# configuration_SCAM.net
KiCad netlist of a schematic drawn in Altium Designer
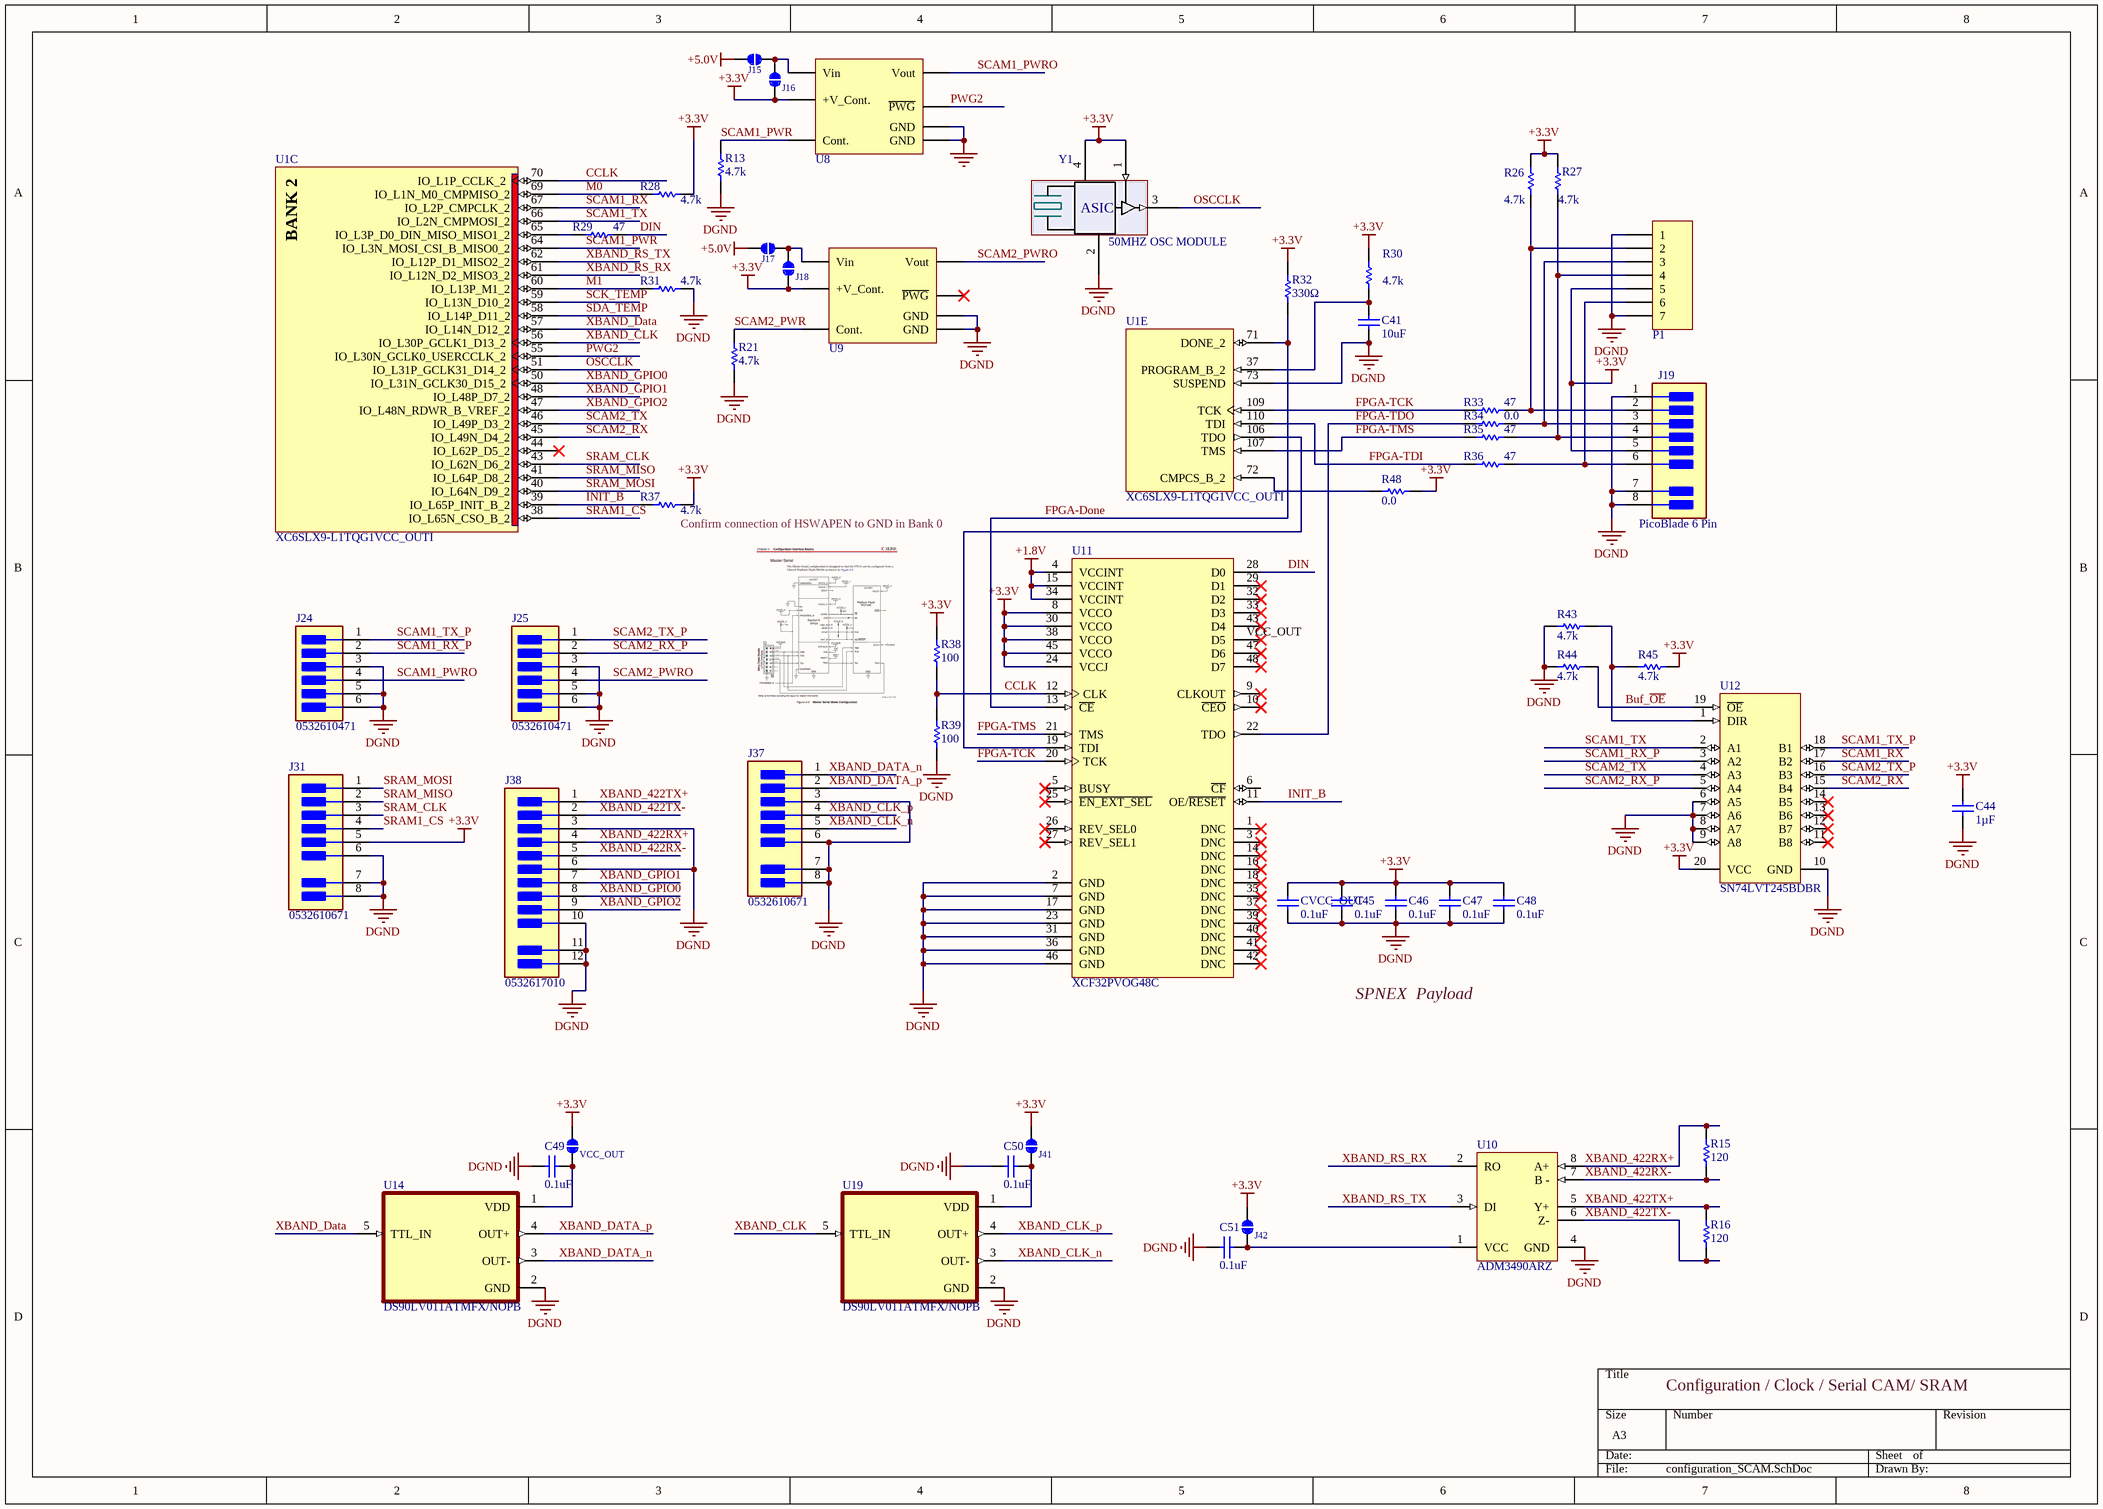
[diagram p0: configuration_SCAM.SchDoc]

(export (version "E")
  (design (tool "Eeschema 10.0.6"))
  (components
    (comp (ref "C41")
      (value "10uF")
      (footprint "capc3216n")
      (description "Capacitor")
      (fields (field (name "Comment") "Cap Semi"))
      (libsource (lib "Spnex_lib") (part "Cap_CER_10U_10V_1206"))
    )
    (comp (ref "C44")
      (value "Cap_CER_1U_10V_0603")
      (footprint "0603CAP")
      (description "Capacitor")
      (fields
        (field (name "MANUFACTURER") "Taiyo Yuden")
        (field (name "MANUFACTURER PART NUMBER") "LMK107B7105KA-T")
        (field (name "CAPACITANCE") "1µF")
      )
      (libsource (lib "SPNeX_NewPL") (part "Cap_CER_1U_10V_0603"))
    )
    (comp (ref "C45")
      (value "0.1uF")
      (footprint "0805CAP")
      (description "Surface Mount Ceramic Multilayer Capacitor 0.1uF 10% X7R 16V 0805 Paper T/R")
      (fields
        (field (name "MANUFACTURER") "Yageo")
        (field (name "MANUFACTURER PART NUMBER") "CC0805KRX7R7BB104")
      )
      (libsource (lib "SPNeX_NewPL") (part "CAP_CER_0.1uf_10V_0805"))
    )
    (comp (ref "C46")
      (value "0.1uF")
      (footprint "0805CAP")
      (description "Surface Mount Ceramic Multilayer Capacitor 0.1uF 10% X7R 16V 0805 Paper T/R")
      (fields
        (field (name "MANUFACTURER") "Yageo")
        (field (name "MANUFACTURER PART NUMBER") "CC0805KRX7R7BB104")
      )
      (libsource (lib "SPNeX_NewPL") (part "CAP_CER_0.1uf_10V_0805"))
    )
    (comp (ref "C47")
      (value "0.1uF")
      (footprint "0805CAP")
      (description "Surface Mount Ceramic Multilayer Capacitor 0.1uF 10% X7R 16V 0805 Paper T/R")
      (fields
        (field (name "MANUFACTURER") "Yageo")
        (field (name "MANUFACTURER PART NUMBER") "CC0805KRX7R7BB104")
      )
      (libsource (lib "SPNeX_NewPL") (part "CAP_CER_0.1uf_10V_0805"))
    )
    (comp (ref "C48")
      (value "0.1uF")
      (footprint "0805CAP")
      (description "Surface Mount Ceramic Multilayer Capacitor 0.1uF 10% X7R 16V 0805 Paper T/R")
      (fields
        (field (name "MANUFACTURER") "Yageo")
        (field (name "MANUFACTURER PART NUMBER") "CC0805KRX7R7BB104")
      )
      (libsource (lib "SPNeX_NewPL") (part "CAP_CER_0.1uf_10V_0805"))
    )
    (comp (ref "C49")
      (value "0.1uF")
      (footprint "0805CAP")
      (description "Surface Mount Ceramic Multilayer Capacitor 0.1uF 10% X7R 16V 0805 Paper T/R")
      (fields
        (field (name "MANUFACTURER") "Yageo")
        (field (name "MANUFACTURER PART NUMBER") "CC0805KRX7R7BB104")
      )
      (libsource (lib "SPNeX_NewPL") (part "CAP_CER_0.1uf_10V_0805"))
    )
    (comp (ref "C50")
      (value "0.1uF")
      (footprint "0805 - CAP")
      (description "CAP CER 0.1UF 16V X7R 0805")
      (fields
        (field (name "MANUFACTURER") "Samsung Electro-Mechanics America, Inc.")
        (field (name "MANUFACTURER PART NUMBER") "CL21B104KOANNNC")
      )
      (libsource (lib "Kh_Lib") (part "Cap_CER_0.1U_16V_0805"))
    )
    (comp (ref "C51")
      (value "0.1uF")
      (footprint "0805 - CAP")
      (description "CAP CER 0.1UF 16V X7R 0805")
      (fields
        (field (name "MANUFACTURER") "Samsung Electro-Mechanics America, Inc.")
        (field (name "MANUFACTURER PART NUMBER") "CL21B104KOANNNC")
      )
      (libsource (lib "Kh_Lib") (part "Cap_CER_0.1U_16V_0805"))
    )
    (comp (ref "CVCC_OUT")
      (value "0.1uF")
      (footprint "0805CAP")
      (description "Surface Mount Ceramic Multilayer Capacitor 0.1uF 10% X7R 16V 0805 Paper T/R")
      (fields
        (field (name "MANUFACTURER") "Yageo")
        (field (name "MANUFACTURER PART NUMBER") "CC0805KRX7R7BB104")
      )
      (libsource (lib "SPNeX_NewPL") (part "CAP_CER_0.1uf_10V_0805"))
    )
    (comp (ref "J15")
      (value "JUMPER")
      (footprint "SJMP")
      (description "OPTION SELECTION PAD")
      (libsource (lib "") (part "JUMPER_1"))
    )
    (comp (ref "J16")
      (value "JUMPER")
      (footprint "SJMP")
      (description "OPTION SELECTION PAD")
      (libsource (lib "Spnex_lib") (part "JUMPER"))
    )
    (comp (ref "J17")
      (value "JUMPER")
      (footprint "SJMP")
      (description "OPTION SELECTION PAD")
      (libsource (lib "") (part "JUMPER_1"))
    )
    (comp (ref "J18")
      (value "JUMPER")
      (footprint "SJMP")
      (description "OPTION SELECTION PAD")
      (libsource (lib "Spnex_lib") (part "JUMPER"))
    )
    (comp (ref "J19")
      (value "PicoBlade 6 Pin")
      (footprint "Molex_6RA_MFG")
      (description "1.25mm (.049\") Pitch PicoBlade Header, Surface Mount, Right Angle, Lead-free, 6 Circuits")
      (fields (field (name "MANUFACTURER") "Molex") (field (name "MANUFACTURER PART NUMBER") "0532610671"))
      (libsource (lib "Spnex_lib") (part "0532610671"))
    )
    (comp (ref "J24")
      (value "0532610471")
      (footprint "Molex_4RA_MFG")
      (description "Conn Shrouded Header (4 Sides) HDR 4 POS 1.25mm Solder RA Side Entry SMD PicoBlade™ T/R")
      (fields (field (name "MANUFACTURER") "Molex") (field (name "MANUFACTURER PART NUMBER") "53261-0471"))
      (libsource (lib "SPNeX_NewPL") (part "0532610471"))
    )
    (comp (ref "J25")
      (value "0532610471")
      (footprint "Molex_4RA_MFG")
      (description "Conn Shrouded Header (4 Sides) HDR 4 POS 1.25mm Solder RA Side Entry SMD PicoBlade™ T/R")
      (fields (field (name "MANUFACTURER") "Molex") (field (name "MANUFACTURER PART NUMBER") "53261-0471"))
      (libsource (lib "SPNeX_NewPL") (part "0532610471"))
    )
    (comp (ref "J31")
      (value "0532610671")
      (footprint "Molex_6RA_MFG")
      (description "1.25mm (.049\") Pitch PicoBlade Header, Surface Mount, Right Angle, Lead-free, 6 Circuits")
      (fields (field (name "MANUFACTURER") "Molex"))
      (libsource (lib "Spnex_library") (part "0532610671"))
    )
    (comp (ref "J37")
      (value "0532610671")
      (footprint "Molex_6RA_MFG")
      (description "1.25mm (.049\") Pitch PicoBlade Header, Surface Mount, Right Angle, Lead-free, 6 Circuits")
      (fields (field (name "MANUFACTURER") "Molex"))
      (libsource (lib "Spnex_library") (part "0532610671"))
    )
    (comp (ref "J38")
      (value "0532617010")
      (footprint "Molex_10RA")
      (fields (field (name "MANUFACTURER") "Molex"))
      (libsource (lib "Spnex_library") (part "0532617010"))
    )
    (comp (ref "J41")
      (value "JUMPER")
      (footprint "SJMP")
      (description "OPTION SELECTION PAD")
      (libsource (lib "Kh_Lib") (part "JUMPER"))
    )
    (comp (ref "J42")
      (value "JUMPER")
      (footprint "SJMP")
      (description "OPTION SELECTION PAD")
      (libsource (lib "Kh_Lib") (part "JUMPER"))
    )
    (comp (ref "P1")
      (value "Header 7")
      (footprint "HDR1X7F")
      (description "Header, 7-Pin")
      (fields (field (name "PUBLISHER") "Altium Limited"))
      (libsource (lib "Spnex_lib") (part "Header 7"))
    )
    (comp (ref "R13")
      (value "RES_4.7K_0.1W_0603")
      (footprint "0603RES")
      (description "Resistor")
      (fields
        (field (name "MANUFACTURER") "Stackpole Electronics Inc.")
        (field (name "MANUFACTURER PART NUMBER") "RMCF0603JT4K70")
        (field (name "RESISTANCE (OHMS)") "4.7k")
      )
      (libsource (lib "Spnex_lib") (part "RES_4.7K_0.1W_0603"))
    )
    (comp (ref "R15")
      (value "RES_120_0.25W_0603")
      (footprint "0603RES")
      (description "RES SMD 120 OHM 5% 1/4W 0603")
      (fields
        (field (name "MANUFACTURER") "Rohm Semiconductor")
        (field (name "MANUFACTURER PART NUMBER") "ESR03EZPJ121")
        (field (name "RESISTANCE (OHMS)") "120")
      )
      (libsource (lib "Spnex_library") (part "RES_120_0.25W_0603"))
    )
    (comp (ref "R16")
      (value "RES_120_0.25W_0603")
      (footprint "0603RES")
      (description "RES SMD 120 OHM 5% 1/4W 0603")
      (fields
        (field (name "MANUFACTURER") "Rohm Semiconductor")
        (field (name "MANUFACTURER PART NUMBER") "ESR03EZPJ121")
        (field (name "RESISTANCE (OHMS)") "120")
      )
      (libsource (lib "Spnex_library") (part "RES_120_0.25W_0603"))
    )
    (comp (ref "R21")
      (value "RES_4.7K_0.1W_0603")
      (footprint "0603RES")
      (description "Resistor")
      (fields
        (field (name "MANUFACTURER") "Stackpole Electronics Inc.")
        (field (name "MANUFACTURER PART NUMBER") "RMCF0603JT4K70")
        (field (name "RESISTANCE (OHMS)") "4.7k")
      )
      (libsource (lib "Spnex_lib") (part "RES_4.7K_0.1W_0603"))
    )
    (comp (ref "R26")
      (value "RES_4.7K_0.1W_0603")
      (footprint "0603RES")
      (description "Resistor")
      (fields
        (field (name "MANUFACTURER") "Stackpole Electronics Inc.")
        (field (name "MANUFACTURER PART NUMBER") "RMCF0603JT4K70")
        (field (name "RESISTANCE (OHMS)") "4.7k")
      )
      (libsource (lib "Spnex_lib") (part "RES_4.7K_0.1W_0603"))
    )
    (comp (ref "R27")
      (value "RES_4.7K_0.1W_0603")
      (footprint "0603RES")
      (description "Resistor")
      (fields
        (field (name "MANUFACTURER") "Stackpole Electronics Inc.")
        (field (name "MANUFACTURER PART NUMBER") "RMCF0603JT4K70")
        (field (name "RESISTANCE (OHMS)") "4.7k")
      )
      (libsource (lib "Spnex_lib") (part "RES_4.7K_0.1W_0603"))
    )
    (comp (ref "R28")
      (value "RES_4.7K_0.1W_0603")
      (footprint "0603RES")
      (description "Resistor")
      (fields
        (field (name "MANUFACTURER") "Stackpole Electronics Inc.")
        (field (name "MANUFACTURER PART NUMBER") "RMCF0603JT4K70")
        (field (name "RESISTANCE (OHMS)") "4.7k")
      )
      (libsource (lib "Spnex_lib") (part "RES_4.7K_0.1W_0603"))
    )
    (comp (ref "R29")
      (value "RES_47R_0.25W_0805")
      (footprint "0603RES")
      (description "RES SMD 47 OHM 5% 0.4W 0805")
      (fields
        (field (name "MANUFACTURER") "Rohm Semiconductor")
        (field (name "MANUFACTURER PART NUMBER") "ESR10EZPJ470")
        (field (name "RESISTANCE (OHMS)") "47")
      )
      (libsource (lib "Spnex_lib") (part "RES_47R_0.25W_0805"))
    )
    (comp (ref "R30")
      (value "RES_4.7K_0.1W_0603")
      (footprint "0603RES")
      (description "Resistor")
      (fields
        (field (name "MANUFACTURER") "Stackpole Electronics Inc.")
        (field (name "MANUFACTURER PART NUMBER") "RMCF0603JT4K70")
        (field (name "RESISTANCE (OHMS)") "4.7k")
      )
      (libsource (lib "Spnex_lib") (part "RES_4.7K_0.1W_0603"))
    )
    (comp (ref "R31")
      (value "RES_4.7K_0.1W_0603")
      (footprint "0603RES")
      (description "Resistor")
      (fields
        (field (name "MANUFACTURER") "Stackpole Electronics Inc.")
        (field (name "MANUFACTURER PART NUMBER") "RMCF0603JT4K70")
        (field (name "RESISTANCE (OHMS)") "4.7k")
      )
      (libsource (lib "Spnex_lib") (part "RES_4.7K_0.1W_0603"))
    )
    (comp (ref "R32")
      (value "RES_330 Ohm_0603")
      (footprint "0603")
      (description "Res Thick Film 0603 330 Ohm 5% 0.1W(1/10W) +/-200ppm/ßC Pad SMD Automotive T/R")
      (fields
        (field (name "MANUFACTURER") "Panasonic")
        (field (name "MANUFACTURER PART NUMBER") "ERJ-3GEYJ331V")
        (field (name "RESISTANCE") "330Ω")
      )
      (libsource (lib "Spnex_lib") (part "RES_330 Ohm_0603"))
    )
    (comp (ref "R33")
      (value "RES_47R_0.25W_0805")
      (footprint "0603RES")
      (description "RES SMD 47 OHM 5% 0.4W 0805")
      (fields
        (field (name "MANUFACTURER") "Rohm Semiconductor")
        (field (name "MANUFACTURER PART NUMBER") "ESR10EZPJ470")
        (field (name "RESISTANCE (OHMS)") "47")
      )
      (libsource (lib "Spnex_lib") (part "RES_47R_0.25W_0805"))
    )
    (comp (ref "R34")
      (value "RES_0_0.1W_0603")
      (footprint "0603RES")
      (description "Resistor")
      (fields
        (field (name "MANUFACTURER") "Samsung Electro-Mechanics America, Inc.")
        (field (name "MANUFACTURER PART NUMBER") "RC1608J000CS")
        (field (name "RESISTANCE (OHMS)") "0.0")
      )
      (libsource (lib "Spnex_lib") (part "RES_0_0.1W_0603"))
    )
    (comp (ref "R35")
      (value "RES_47R_0.25W_0805")
      (footprint "0603RES")
      (description "RES SMD 47 OHM 5% 0.4W 0805")
      (fields
        (field (name "MANUFACTURER") "Rohm Semiconductor")
        (field (name "MANUFACTURER PART NUMBER") "ESR10EZPJ470")
        (field (name "RESISTANCE (OHMS)") "47")
      )
      (libsource (lib "Spnex_lib") (part "RES_47R_0.25W_0805"))
    )
    (comp (ref "R36")
      (value "RES_47R_0.25W_0805")
      (footprint "0603RES")
      (description "RES SMD 47 OHM 5% 0.4W 0805")
      (fields
        (field (name "MANUFACTURER") "Rohm Semiconductor")
        (field (name "MANUFACTURER PART NUMBER") "ESR10EZPJ470")
        (field (name "RESISTANCE (OHMS)") "47")
      )
      (libsource (lib "Spnex_lib") (part "RES_47R_0.25W_0805"))
    )
    (comp (ref "R37")
      (value "RES_4.7K_0.1W_0603")
      (footprint "0603RES")
      (description "Resistor")
      (fields
        (field (name "MANUFACTURER") "Stackpole Electronics Inc.")
        (field (name "MANUFACTURER PART NUMBER") "RMCF0603JT4K70")
        (field (name "RESISTANCE (OHMS)") "4.7k")
      )
      (libsource (lib "Spnex_lib") (part "RES_4.7K_0.1W_0603"))
    )
    (comp (ref "R38")
      (value "RES_100_0.1W_0603")
      (footprint "0603RES")
      (description "Resistor")
      (fields
        (field (name "MANUFACTURER") "Stackpole Electronics Inc.")
        (field (name "MANUFACTURER PART NUMBER") "RMCF0603JT100R")
        (field (name "RESISTANCE (OHMS)") "100")
      )
      (libsource (lib "Spnex_lib") (part "RES_100_0.1W_0603"))
    )
    (comp (ref "R39")
      (value "RES_100_0.1W_0603")
      (footprint "0603RES")
      (description "Resistor")
      (fields
        (field (name "MANUFACTURER") "Stackpole Electronics Inc.")
        (field (name "MANUFACTURER PART NUMBER") "RMCF0603JT100R")
        (field (name "RESISTANCE (OHMS)") "100")
      )
      (libsource (lib "Spnex_lib") (part "RES_100_0.1W_0603"))
    )
    (comp (ref "R43")
      (value "RES_4.7K_0.1W_0603")
      (footprint "0603RES")
      (description "Resistor")
      (fields
        (field (name "MANUFACTURER") "Stackpole Electronics Inc.")
        (field (name "MANUFACTURER PART NUMBER") "RMCF0603JT4K70")
        (field (name "RESISTANCE (OHMS)") "4.7k")
      )
      (libsource (lib "SPNeX_NewPL") (part "RES_4.7K_0.1W_0603"))
    )
    (comp (ref "R44")
      (value "RES_4.7K_0.1W_0603")
      (footprint "0603RES")
      (description "Resistor")
      (fields
        (field (name "MANUFACTURER") "Stackpole Electronics Inc.")
        (field (name "MANUFACTURER PART NUMBER") "RMCF0603JT4K70")
        (field (name "RESISTANCE (OHMS)") "4.7k")
      )
      (libsource (lib "SPNeX_NewPL") (part "RES_4.7K_0.1W_0603"))
    )
    (comp (ref "R45")
      (value "RES_4.7K_0.1W_0603")
      (footprint "0603RES")
      (description "Resistor")
      (fields
        (field (name "MANUFACTURER") "Stackpole Electronics Inc.")
        (field (name "MANUFACTURER PART NUMBER") "RMCF0603JT4K70")
        (field (name "RESISTANCE (OHMS)") "4.7k")
      )
      (libsource (lib "SPNeX_NewPL") (part "RES_4.7K_0.1W_0603"))
    )
    (comp (ref "R48")
      (value "RES_0_0.1W_0603")
      (footprint "0603RES")
      (description "Resistor")
      (fields
        (field (name "MANUFACTURER") "Samsung Electro-Mechanics America, Inc.")
        (field (name "MANUFACTURER PART NUMBER") "RC1608J000CS")
        (field (name "RESISTANCE (OHMS)") "0.0")
      )
      (libsource (lib "Spnex_library") (part "RES_0_0.1W_0603"))
    )
    (comp (ref "U1")
      (value "XC6SLX9-L1TQG1VCC_OUTI")
      (footprint "TQG144_M")
      (fields (field (name "PUBLISHER") "Altium Limited"))
      (libsource (lib "Spnex_lib") (part "XC6SLX9-L1TQG144I"))
    )
    (comp (ref "U8")
      (value "LTC3461 module")
      (footprint "OCPfootprint")
      (libsource (lib "Kh_Lib") (part "OCP_Module"))
    )
    (comp (ref "U9")
      (value "LTC3461 module")
      (footprint "OCPfootprint")
      (libsource (lib "Kh_Lib") (part "OCP_Module"))
    )
    (comp (ref "U10")
      (value "ADM3490ARZ")
      (footprint "Soic8_IPCA")
      (description "Single Transmitter/Receiver RS-422/RS-485 8-Pin SOIC N T/R")
      (fields
        (field (name "MANUFACTURER") "Analog Devices")
        (field (name "MANUFACTURER PART NUMBER") "ADM3490ARZ-REEL7")
      )
      (libsource (lib "Spnex_library") (part "ADM3490ARZ"))
    )
    (comp (ref "U11")
      (value "XCF32PVOG48C")
      (footprint "VOG48")
      (fields (field (name "MANUFACTURER") "Xilinx Inc."))
      (libsource (lib "Spnex_lib") (part "XCF32PVOG48C"))
    )
    (comp (ref "U12")
      (value "SN74LVT245BDBR")
      (footprint "DB0020A_M")
      (description "3.3-V ABT Octal Bus Transceivers With 3-State Outputs, DB0020A, LARGE T&R")
      (fields
        (field (name "GENERIC PART NUMBER") "SN74LVT245B")
        (field (name "MANUFACTURER") "Texas Instruments")
      )
      (libsource (lib "Spnex_lib") (part "SN74LVT245BDBR"))
    )
    (comp (ref "U14")
      (value "DS90LV011ATMFX/NOPB")
      (footprint "SOT95P280X145-5N")
      (libsource (lib "Kh_Lib") (part "DS90LV011ATMFX/NOPB"))
    )
    (comp (ref "U19")
      (value "DS90LV011ATMFX/NOPB")
      (footprint "SOT95P280X145-5N")
      (libsource (lib "Kh_Lib") (part "DS90LV011ATMFX/NOPB"))
    )
    (comp (ref "VCC_OUT")
      (value "JUMPER")
      (footprint "SJMP")
      (description "OPTION SELECTION PAD")
      (libsource (lib "Kh_Lib") (part "JUMPER"))
    )
    (comp (ref "Y1")
      (value "50MHZ OSC MODULE")
      (footprint "OscModule")
      (libsource (lib "Spnex_lib") (part "OscillatorModule"))
    )
  )
  (nets
    (net (code "1") (name "+1.8V") (class "Default")
      (node (ref "U11") (pin "15") (pinfunction "VCCINT_15") (pintype "power_in"))
      (node (ref "U11") (pin "34") (pinfunction "VCCINT_34") (pintype "power_in"))
      (node (ref "U11") (pin "4") (pinfunction "VCCINT_4") (pintype "power_in"))
    )
    (net (code "2") (name "+3.3V") (class "Default")
      (node (ref "C44") (pin "2") (pinfunction "2_2") (pintype "passive"))
      (node (ref "C45") (pin "2") (pinfunction "2_2") (pintype "passive"))
      (node (ref "C46") (pin "2") (pinfunction "2_2") (pintype "passive"))
      (node (ref "C47") (pin "2") (pinfunction "2_2") (pintype "passive"))
      (node (ref "C48") (pin "2") (pinfunction "2_2") (pintype "passive"))
      (node (ref "CVCC_OUT") (pin "2") (pinfunction "2_2") (pintype "passive"))
      (node (ref "J16") (pin "1") (pinfunction "1_1") (pintype "passive"))
      (node (ref "J18") (pin "1") (pinfunction "1_1") (pintype "passive"))
      (node (ref "J19") (pin "5") (pinfunction "5_5") (pintype "passive"))
      (node (ref "J31") (pin "5") (pinfunction "5_5") (pintype "passive"))
      (node (ref "J41") (pin "2") (pinfunction "2_2") (pintype "passive"))
      (node (ref "J42") (pin "2") (pinfunction "2_2") (pintype "passive"))
      (node (ref "P1") (pin "5") (pinfunction "5_5") (pintype "passive"))
      (node (ref "R26") (pin "2") (pinfunction "2_2") (pintype "passive"))
      (node (ref "R27") (pin "2") (pinfunction "2_2") (pintype "passive"))
      (node (ref "R28") (pin "1") (pinfunction "1_1") (pintype "passive"))
      (node (ref "R30") (pin "2") (pinfunction "2_2") (pintype "passive"))
      (node (ref "R32") (pin "2") (pinfunction "2_2") (pintype "passive"))
      (node (ref "R37") (pin "1") (pinfunction "1_1") (pintype "passive"))
      (node (ref "R38") (pin "2") (pinfunction "2_2") (pintype "passive"))
      (node (ref "R45") (pin "1") (pinfunction "1_1") (pintype "passive"))
      (node (ref "R48") (pin "2") (pinfunction "2_2") (pintype "passive"))
      (node (ref "U11") (pin "24") (pinfunction "VCCJ_24") (pintype "power_in"))
      (node (ref "U11") (pin "30") (pinfunction "VCCO_30") (pintype "power_in"))
      (node (ref "U11") (pin "38") (pinfunction "VCCO_38") (pintype "power_in"))
      (node (ref "U11") (pin "45") (pinfunction "VCCO_45") (pintype "power_in"))
      (node (ref "U11") (pin "8") (pinfunction "VCCO_8") (pintype "power_in"))
      (node (ref "U12") (pin "20") (pinfunction "VCC_20") (pintype "power_in"))
      (node (ref "U8") (pin "5") (pinfunction "+V_Cont._5") (pintype "passive"))
      (node (ref "U9") (pin "5") (pinfunction "+V_Cont._5") (pintype "passive"))
      (node (ref "VCC_OUT") (pin "2") (pinfunction "2_2") (pintype "passive"))
      (node (ref "Y1") (pin "1") (pinfunction "E/D_1") (pintype "input"))
      (node (ref "Y1") (pin "4") (pinfunction "VDD_4") (pintype "power_in"))
    )
    (net (code "3") (name "+5.0V") (class "Default")
      (node (ref "J15") (pin "2") (pinfunction "2_2") (pintype "passive"))
      (node (ref "J17") (pin "2") (pinfunction "2_2") (pintype "passive"))
    )
    (net (code "4") (name "/Buf_~{OE}") (class "Default")
      (node (ref "R44") (pin "1") (pinfunction "1_1") (pintype "passive"))
      (node (ref "U12") (pin "19") (pinfunction "~{OE}_19") (pintype "input"))
    )
    (net (code "5") (name "/CCLK") (class "Default")
      (node (ref "R38") (pin "1") (pinfunction "1_1") (pintype "passive"))
      (node (ref "R39") (pin "2") (pinfunction "2_2") (pintype "passive"))
      (node (ref "U1") (pin "70") (pinfunction "IO_L1P_CCLK_2_70") (pintype "bidirectional"))
      (node (ref "U11") (pin "12") (pinfunction "CLK_12") (pintype "input"))
    )
    (net (code "6") (name "/DIN") (class "Default")
      (node (ref "R29") (pin "2") (pinfunction "2_2") (pintype "passive"))
      (node (ref "U11") (pin "28") (pinfunction "D0_28") (pintype "tri_state"))
    )
    (net (code "7") (name "/FPGA-Done") (class "Default")
      (node (ref "R32") (pin "1") (pinfunction "1_1") (pintype "passive"))
      (node (ref "U1") (pin "71") (pinfunction "DONE_2_71") (pintype "bidirectional"))
      (node (ref "U11") (pin "13") (pinfunction "~{CE}_13") (pintype "input"))
    )
    (net (code "8") (name "/FPGA-TCK") (class "Default")
      (node (ref "R33") (pin "1") (pinfunction "1_1") (pintype "passive"))
      (node (ref "U1") (pin "109") (pinfunction "TCK_109") (pintype "input"))
      (node (ref "U11") (pin "20") (pinfunction "TCK_20") (pintype "input"))
    )
    (net (code "9") (name "/FPGA-TDI") (class "Default")
      (node (ref "R36") (pin "1") (pinfunction "1_1") (pintype "passive"))
      (node (ref "U1") (pin "110") (pinfunction "TDI_110") (pintype "input"))
    )
    (net (code "10") (name "/FPGA-TDO") (class "Default")
      (node (ref "R34") (pin "1") (pinfunction "1_1") (pintype "passive"))
      (node (ref "U11") (pin "22") (pinfunction "TDO_22") (pintype "output"))
    )
    (net (code "11") (name "/FPGA-TMS") (class "Default")
      (node (ref "R35") (pin "1") (pinfunction "1_1") (pintype "passive"))
      (node (ref "U1") (pin "107") (pinfunction "TMS_107") (pintype "input"))
      (node (ref "U11") (pin "21") (pinfunction "TMS_21") (pintype "input"))
    )
    (net (code "12") (name "/INIT_B") (class "Default")
      (node (ref "R37") (pin "2") (pinfunction "2_2") (pintype "passive"))
      (node (ref "U1") (pin "39") (pinfunction "IO_L65P_INIT_B_2_39") (pintype "bidirectional"))
      (node (ref "U11") (pin "11") (pinfunction "OE/~{RESET}_11") (pintype "bidirectional"))
    )
    (net (code "13") (name "/M0") (class "Default")
      (node (ref "R28") (pin "2") (pinfunction "2_2") (pintype "passive"))
      (node (ref "U1") (pin "69") (pinfunction "IO_L1N_M0_CMPMISO_2_69") (pintype "bidirectional"))
    )
    (net (code "14") (name "/M1") (class "Default")
      (node (ref "R31") (pin "2") (pinfunction "2_2") (pintype "passive"))
      (node (ref "U1") (pin "60") (pinfunction "IO_L13P_M1_2_60") (pintype "bidirectional"))
    )
    (net (code "15") (name "/OSCCLK") (class "Default")
      (node (ref "U1") (pin "51") (pinfunction "IO_L31P_GCLK31_D14_2_51") (pintype "bidirectional"))
      (node (ref "Y1") (pin "3") (pinfunction "Output_3") (pintype "output"))
    )
    (net (code "16") (name "/PWG2") (class "Default")
      (node (ref "U1") (pin "55") (pinfunction "IO_L30N_GCLK0_USERCCLK_2_55") (pintype "bidirectional"))
      (node (ref "U8") (pin "7") (pinfunction "~{PWG}_7") (pintype "passive"))
    )
    (net (code "17") (name "/SCAM1_PWR") (class "Default")
      (node (ref "R13") (pin "1") (pinfunction "1_1") (pintype "passive"))
      (node (ref "U1") (pin "64") (pinfunction "IO_L3N_MOSI_CSI_B_MISO0_2_64") (pintype "bidirectional"))
      (node (ref "U8") (pin "6") (pinfunction "Cont._6") (pintype "passive"))
    )
    (net (code "18") (name "/SCAM1_PWRO") (class "Default")
      (node (ref "J24") (pin "4") (pinfunction "4_4") (pintype "passive"))
      (node (ref "U8") (pin "3") (pinfunction "Vout_3") (pintype "passive"))
    )
    (net (code "19") (name "/SCAM1_RX") (class "Default")
      (node (ref "U1") (pin "67") (pinfunction "IO_L2P_CMPCLK_2_67") (pintype "bidirectional"))
      (node (ref "U12") (pin "17") (pinfunction "B2_17") (pintype "bidirectional"))
    )
    (net (code "20") (name "/SCAM1_RX_P") (class "Default")
      (node (ref "J24") (pin "2") (pinfunction "2_2") (pintype "passive"))
      (node (ref "U12") (pin "3") (pinfunction "A2_3") (pintype "bidirectional"))
    )
    (net (code "21") (name "/SCAM1_TX") (class "Default")
      (node (ref "U1") (pin "66") (pinfunction "IO_L2N_CMPMOSI_2_66") (pintype "bidirectional"))
      (node (ref "U12") (pin "2") (pinfunction "A1_2") (pintype "bidirectional"))
    )
    (net (code "22") (name "/SCAM1_TX_P") (class "Default")
      (node (ref "J24") (pin "1") (pinfunction "1_1") (pintype "passive"))
      (node (ref "U12") (pin "18") (pinfunction "B1_18") (pintype "bidirectional"))
    )
    (net (code "23") (name "/SCAM2_PWR") (class "Default")
      (node (ref "R21") (pin "1") (pinfunction "1_1") (pintype "passive"))
      (node (ref "U9") (pin "6") (pinfunction "Cont._6") (pintype "passive"))
    )
    (net (code "24") (name "/SCAM2_PWRO") (class "Default")
      (node (ref "J25") (pin "4") (pinfunction "4_4") (pintype "passive"))
      (node (ref "U9") (pin "3") (pinfunction "Vout_3") (pintype "passive"))
    )
    (net (code "25") (name "/SCAM2_RX") (class "Default")
      (node (ref "U1") (pin "45") (pinfunction "IO_L49N_D4_2_45") (pintype "bidirectional"))
      (node (ref "U12") (pin "15") (pinfunction "B4_15") (pintype "bidirectional"))
    )
    (net (code "26") (name "/SCAM2_RX_P") (class "Default")
      (node (ref "J25") (pin "2") (pinfunction "2_2") (pintype "passive"))
      (node (ref "U12") (pin "5") (pinfunction "A4_5") (pintype "bidirectional"))
    )
    (net (code "27") (name "/SCAM2_TX") (class "Default")
      (node (ref "U1") (pin "46") (pinfunction "IO_L49P_D3_2_46") (pintype "bidirectional"))
      (node (ref "U12") (pin "4") (pinfunction "A3_4") (pintype "bidirectional"))
    )
    (net (code "28") (name "/SCAM2_TX_P") (class "Default")
      (node (ref "J25") (pin "1") (pinfunction "1_1") (pintype "passive"))
      (node (ref "U12") (pin "16") (pinfunction "B3_16") (pintype "bidirectional"))
    )
    (net (code "29") (name "/SCK_TEMP") (class "Default")
      (node (ref "U1") (pin "59") (pinfunction "IO_L13N_D10_2_59") (pintype "bidirectional"))
    )
    (net (code "30") (name "/SDA_TEMP") (class "Default")
      (node (ref "U1") (pin "58") (pinfunction "IO_L14P_D11_2_58") (pintype "bidirectional"))
    )
    (net (code "31") (name "/SRAM1_CS") (class "Default")
      (node (ref "J31") (pin "4") (pinfunction "4_4") (pintype "passive"))
      (node (ref "U1") (pin "38") (pinfunction "IO_L65N_CSO_B_2_38") (pintype "bidirectional"))
    )
    (net (code "32") (name "/SRAM_CLK") (class "Default")
      (node (ref "J31") (pin "3") (pinfunction "3_3") (pintype "passive"))
      (node (ref "U1") (pin "43") (pinfunction "IO_L62N_D6_2_43") (pintype "bidirectional"))
    )
    (net (code "33") (name "/SRAM_MISO") (class "Default")
      (node (ref "J31") (pin "2") (pinfunction "2_2") (pintype "passive"))
      (node (ref "U1") (pin "41") (pinfunction "IO_L64P_D8_2_41") (pintype "bidirectional"))
    )
    (net (code "34") (name "/SRAM_MOSI") (class "Default")
      (node (ref "J31") (pin "1") (pinfunction "1_1") (pintype "passive"))
      (node (ref "U1") (pin "40") (pinfunction "IO_L64N_D9_2_40") (pintype "bidirectional"))
    )
    (net (code "35") (name "/XBAND_422RX+") (class "Default")
      (node (ref "J38") (pin "4") (pinfunction "4_4") (pintype "passive"))
      (node (ref "R15") (pin "2") (pinfunction "2_2") (pintype "passive"))
      (node (ref "U10") (pin "8") (pinfunction "A+_8") (pintype "input"))
    )
    (net (code "36") (name "/XBAND_422RX-") (class "Default")
      (node (ref "J38") (pin "5") (pinfunction "5_5") (pintype "passive"))
      (node (ref "R15") (pin "1") (pinfunction "1_1") (pintype "passive"))
      (node (ref "U10") (pin "7") (pinfunction "B_-_7") (pintype "input"))
    )
    (net (code "37") (name "/XBAND_422TX+") (class "Default")
      (node (ref "J38") (pin "1") (pinfunction "1_1") (pintype "passive"))
      (node (ref "R16") (pin "2") (pinfunction "2_2") (pintype "passive"))
      (node (ref "U10") (pin "5") (pinfunction "Y+_5") (pintype "tri_state"))
    )
    (net (code "38") (name "/XBAND_422TX-") (class "Default")
      (node (ref "J38") (pin "2") (pinfunction "2_2") (pintype "passive"))
      (node (ref "R16") (pin "1") (pinfunction "1_1") (pintype "passive"))
      (node (ref "U10") (pin "6") (pinfunction "Z-_6") (pintype "tri_state"))
    )
    (net (code "39") (name "/XBAND_CLK") (class "Default")
      (node (ref "U1") (pin "56") (pinfunction "IO_L30P_GCLK1_D13_2_56") (pintype "bidirectional"))
      (node (ref "U19") (pin "5") (pinfunction "TTL_IN_5") (pintype "input"))
    )
    (net (code "40") (name "/XBAND_CLK_n") (class "Default")
      (node (ref "J37") (pin "5") (pinfunction "5_5") (pintype "passive"))
      (node (ref "U19") (pin "3") (pinfunction "OUT-_3") (pintype "output"))
    )
    (net (code "41") (name "/XBAND_CLK_p") (class "Default")
      (node (ref "J37") (pin "4") (pinfunction "4_4") (pintype "passive"))
      (node (ref "U19") (pin "4") (pinfunction "OUT+_4") (pintype "output"))
    )
    (net (code "42") (name "/XBAND_DATA_n") (class "Default")
      (node (ref "J37") (pin "1") (pinfunction "1_1") (pintype "passive"))
      (node (ref "U14") (pin "3") (pinfunction "OUT-_3") (pintype "output"))
    )
    (net (code "43") (name "/XBAND_DATA_p") (class "Default")
      (node (ref "J37") (pin "2") (pinfunction "2_2") (pintype "passive"))
      (node (ref "U14") (pin "4") (pinfunction "OUT+_4") (pintype "output"))
    )
    (net (code "44") (name "/XBAND_Data") (class "Default")
      (node (ref "U1") (pin "57") (pinfunction "IO_L14N_D12_2_57") (pintype "bidirectional"))
      (node (ref "U14") (pin "5") (pinfunction "TTL_IN_5") (pintype "input"))
    )
    (net (code "45") (name "/XBAND_GPIO0") (class "Default")
      (node (ref "J38") (pin "8") (pinfunction "8_8") (pintype "passive"))
      (node (ref "U1") (pin "50") (pinfunction "IO_L31N_GCLK30_D15_2_50") (pintype "bidirectional"))
    )
    (net (code "46") (name "/XBAND_GPIO1") (class "Default")
      (node (ref "J38") (pin "7") (pinfunction "7_7") (pintype "passive"))
      (node (ref "U1") (pin "48") (pinfunction "IO_L48P_D7_2_48") (pintype "bidirectional"))
    )
    (net (code "47") (name "/XBAND_GPIO2") (class "Default")
      (node (ref "J38") (pin "9") (pinfunction "9_9") (pintype "passive"))
      (node (ref "U1") (pin "47") (pinfunction "IO_L48N_RDWR_B_VREF_2_47") (pintype "bidirectional"))
    )
    (net (code "48") (name "/XBAND_RS_RX") (class "Default")
      (node (ref "U1") (pin "61") (pinfunction "IO_L12N_D2_MISO3_2_61") (pintype "bidirectional"))
      (node (ref "U10") (pin "2") (pinfunction "RO_2") (pintype "tri_state"))
    )
    (net (code "49") (name "/XBAND_RS_TX") (class "Default")
      (node (ref "U1") (pin "62") (pinfunction "IO_L12P_D1_MISO2_2_62") (pintype "bidirectional"))
      (node (ref "U10") (pin "3") (pinfunction "DI_3") (pintype "input"))
    )
    (net (code "50") (name "DGND") (class "Default")
      (node (ref "C41") (pin "1") (pinfunction "1_1") (pintype "passive"))
      (node (ref "C44") (pin "1") (pinfunction "1_1") (pintype "passive"))
      (node (ref "C45") (pin "1") (pinfunction "1_1") (pintype "passive"))
      (node (ref "C46") (pin "1") (pinfunction "1_1") (pintype "passive"))
      (node (ref "C47") (pin "1") (pinfunction "1_1") (pintype "passive"))
      (node (ref "C48") (pin "1") (pinfunction "1_1") (pintype "passive"))
      (node (ref "C49") (pin "2") (pinfunction "2_2") (pintype "passive"))
      (node (ref "C50") (pin "1") (pinfunction "1_1") (pintype "passive"))
      (node (ref "C51") (pin "1") (pinfunction "1_1") (pintype "passive"))
      (node (ref "CVCC_OUT") (pin "1") (pinfunction "1_1") (pintype "passive"))
      (node (ref "J19") (pin "1") (pinfunction "1_1") (pintype "passive"))
      (node (ref "J19") (pin "7") (pinfunction "7_7") (pintype "passive"))
      (node (ref "J19") (pin "8") (pinfunction "8_8") (pintype "passive"))
      (node (ref "J24") (pin "3") (pinfunction "3_3") (pintype "passive"))
      (node (ref "J24") (pin "5") (pinfunction "5_5") (pintype "passive"))
      (node (ref "J24") (pin "6") (pinfunction "6_6") (pintype "passive"))
      (node (ref "J25") (pin "3") (pinfunction "3_3") (pintype "passive"))
      (node (ref "J25") (pin "5") (pinfunction "5_5") (pintype "passive"))
      (node (ref "J25") (pin "6") (pinfunction "6_6") (pintype "passive"))
      (node (ref "J31") (pin "6") (pinfunction "6_6") (pintype "passive"))
      (node (ref "J31") (pin "7") (pinfunction "7_7") (pintype "passive"))
      (node (ref "J31") (pin "8") (pinfunction "8_8") (pintype "passive"))
      (node (ref "J37") (pin "3") (pinfunction "3_3") (pintype "passive"))
      (node (ref "J37") (pin "6") (pinfunction "6_6") (pintype "passive"))
      (node (ref "J37") (pin "7") (pinfunction "7_7") (pintype "passive"))
      (node (ref "J37") (pin "8") (pinfunction "8_8") (pintype "passive"))
      (node (ref "J38") (pin "10") (pinfunction "10_10") (pintype "passive"))
      (node (ref "J38") (pin "11") (pinfunction "11_11") (pintype "passive"))
      (node (ref "J38") (pin "12") (pinfunction "12_12") (pintype "passive"))
      (node (ref "J38") (pin "3") (pinfunction "3_3") (pintype "passive"))
      (node (ref "J38") (pin "6") (pinfunction "6_6") (pintype "passive"))
      (node (ref "P1") (pin "1") (pinfunction "1_1") (pintype "passive"))
      (node (ref "P1") (pin "7") (pinfunction "7_7") (pintype "passive"))
      (node (ref "R13") (pin "2") (pinfunction "2_2") (pintype "passive"))
      (node (ref "R21") (pin "2") (pinfunction "2_2") (pintype "passive"))
      (node (ref "R31") (pin "1") (pinfunction "1_1") (pintype "passive"))
      (node (ref "R39") (pin "1") (pinfunction "1_1") (pintype "passive"))
      (node (ref "R43") (pin "2") (pinfunction "2_2") (pintype "passive"))
      (node (ref "R44") (pin "2") (pinfunction "2_2") (pintype "passive"))
      (node (ref "U1") (pin "73") (pinfunction "SUSPEND_73") (pintype "input"))
      (node (ref "U10") (pin "4") (pinfunction "GND_4") (pintype "power_in"))
      (node (ref "U11") (pin "17") (pinfunction "GND_17") (pintype "power_in"))
      (node (ref "U11") (pin "2") (pinfunction "GND_2") (pintype "power_in"))
      (node (ref "U11") (pin "23") (pinfunction "GND_23") (pintype "power_in"))
      (node (ref "U11") (pin "31") (pinfunction "GND_31") (pintype "power_in"))
      (node (ref "U11") (pin "36") (pinfunction "GND_36") (pintype "power_in"))
      (node (ref "U11") (pin "46") (pinfunction "GND_46") (pintype "power_in"))
      (node (ref "U11") (pin "7") (pinfunction "GND_7") (pintype "power_in"))
      (node (ref "U12") (pin "10") (pinfunction "GND_10") (pintype "power_in"))
      (node (ref "U12") (pin "6") (pinfunction "A5_6") (pintype "bidirectional"))
      (node (ref "U12") (pin "7") (pinfunction "A6_7") (pintype "bidirectional"))
      (node (ref "U12") (pin "8") (pinfunction "A7_8") (pintype "bidirectional"))
      (node (ref "U12") (pin "9") (pinfunction "A8_9") (pintype "bidirectional"))
      (node (ref "U14") (pin "2") (pinfunction "GND_2") (pintype "power_in"))
      (node (ref "U19") (pin "2") (pinfunction "GND_2") (pintype "power_in"))
      (node (ref "U8") (pin "2") (pinfunction "GND_2") (pintype "passive"))
      (node (ref "U8") (pin "4") (pinfunction "GND_4") (pintype "passive"))
      (node (ref "U9") (pin "2") (pinfunction "GND_2") (pintype "passive"))
      (node (ref "U9") (pin "4") (pinfunction "GND_4") (pintype "passive"))
      (node (ref "Y1") (pin "2") (pinfunction "GND_2") (pintype "power_in"))
    )
    (net (code "51") (name "Net-(J19-Pad2)") (class "Default")
      (node (ref "J19") (pin "2") (pinfunction "2_2") (pintype "passive"))
      (node (ref "P1") (pin "2") (pinfunction "2_2") (pintype "passive"))
      (node (ref "R26") (pin "1") (pinfunction "1_1") (pintype "passive"))
      (node (ref "R33") (pin "2") (pinfunction "2_2") (pintype "passive"))
    )
    (net (code "52") (name "Net-(J19-Pad3)") (class "Default")
      (node (ref "J19") (pin "3") (pinfunction "3_3") (pintype "passive"))
      (node (ref "P1") (pin "3") (pinfunction "3_3") (pintype "passive"))
      (node (ref "R34") (pin "2") (pinfunction "2_2") (pintype "passive"))
    )
    (net (code "53") (name "Net-(J19-Pad4)") (class "Default")
      (node (ref "J19") (pin "4") (pinfunction "4_4") (pintype "passive"))
      (node (ref "P1") (pin "4") (pinfunction "4_4") (pintype "passive"))
      (node (ref "R27") (pin "1") (pinfunction "1_1") (pintype "passive"))
      (node (ref "R35") (pin "2") (pinfunction "2_2") (pintype "passive"))
    )
    (net (code "54") (name "Net-(J19-Pad6)") (class "Default")
      (node (ref "J19") (pin "6") (pinfunction "6_6") (pintype "passive"))
      (node (ref "P1") (pin "6") (pinfunction "6_6") (pintype "passive"))
      (node (ref "R36") (pin "2") (pinfunction "2_2") (pintype "passive"))
    )
    (net (code "55") (name "Net-(U1C-IO_L3P_D0_DIN_MISO_MISO1_2)") (class "Default")
      (node (ref "R29") (pin "1") (pinfunction "1_1") (pintype "passive"))
      (node (ref "U1") (pin "65") (pinfunction "IO_L3P_D0_DIN_MISO_MISO1_2_65") (pintype "bidirectional"))
    )
    (net (code "56") (name "Net-(U1E-CMPCS_B_2)") (class "Default")
      (node (ref "R48") (pin "1") (pinfunction "1_1") (pintype "passive"))
      (node (ref "U1") (pin "72") (pinfunction "CMPCS_B_2_72") (pintype "input"))
    )
    (net (code "57") (name "Net-(U1E-PROGRAM_B_2)") (class "Default")
      (node (ref "C41") (pin "2") (pinfunction "2_2") (pintype "passive"))
      (node (ref "R30") (pin "1") (pinfunction "1_1") (pintype "passive"))
      (node (ref "U1") (pin "37") (pinfunction "PROGRAM_B_2_37") (pintype "input"))
    )
    (net (code "58") (name "Net-(U8-Vin)") (class "Default")
      (node (ref "J15") (pin "1") (pinfunction "1_1") (pintype "passive"))
      (node (ref "J16") (pin "2") (pinfunction "2_2") (pintype "passive"))
      (node (ref "U8") (pin "1") (pinfunction "Vin_1") (pintype "passive"))
    )
    (net (code "59") (name "Net-(U9-Vin)") (class "Default")
      (node (ref "J17") (pin "1") (pinfunction "1_1") (pintype "passive"))
      (node (ref "J18") (pin "2") (pinfunction "2_2") (pintype "passive"))
      (node (ref "U9") (pin "1") (pinfunction "Vin_1") (pintype "passive"))
    )
    (net (code "60") (name "Net-(U10-VCC)") (class "Default")
      (node (ref "C51") (pin "2") (pinfunction "2_2") (pintype "passive"))
      (node (ref "J42") (pin "1") (pinfunction "1_1") (pintype "passive"))
      (node (ref "U10") (pin "1") (pinfunction "VCC_1") (pintype "power_in"))
    )
    (net (code "61") (name "Net-(U11-TDI)") (class "Default")
      (node (ref "U1") (pin "106") (pinfunction "TDO_106") (pintype "output"))
      (node (ref "U11") (pin "19") (pinfunction "TDI_19") (pintype "input"))
    )
    (net (code "62") (name "Net-(U12-DIR)") (class "Default")
      (node (ref "R43") (pin "1") (pinfunction "1_1") (pintype "passive"))
      (node (ref "R45") (pin "2") (pinfunction "2_2") (pintype "passive"))
      (node (ref "U12") (pin "1") (pinfunction "DIR_1") (pintype "input"))
    )
    (net (code "63") (name "Net-(U14-VDD)") (class "Default")
      (node (ref "C49") (pin "1") (pinfunction "1_1") (pintype "passive"))
      (node (ref "U14") (pin "1") (pinfunction "VDD_1") (pintype "power_in"))
      (node (ref "VCC_OUT") (pin "1") (pinfunction "1_1") (pintype "passive"))
    )
    (net (code "64") (name "Net-(U19-VDD)") (class "Default")
      (node (ref "C50") (pin "2") (pinfunction "2_2") (pintype "passive"))
      (node (ref "J41") (pin "1") (pinfunction "1_1") (pintype "passive"))
      (node (ref "U19") (pin "1") (pinfunction "VDD_1") (pintype "power_in"))
    )
    (net (code "65") (name "unconnected-(U1C-IO_L62P_D5_2-Pad44)") (class "Default")
      (node (ref "U1") (pin "44") (pinfunction "IO_L62P_D5_2_44") (pintype "bidirectional+no_connect"))
    )
    (net (code "66") (name "unconnected-(U9-~{PWG}-Pad7)") (class "Default")
      (node (ref "U9") (pin "7") (pinfunction "~{PWG}_7") (pintype "passive+no_connect"))
    )
    (net (code "67") (name "unconnected-(U11-BUSY-Pad5)") (class "Default")
      (node (ref "U11") (pin "5") (pinfunction "BUSY_5") (pintype "input+no_connect"))
    )
    (net (code "68") (name "unconnected-(U11-CLKOUT-Pad9)") (class "Default")
      (node (ref "U11") (pin "9") (pinfunction "CLKOUT_9") (pintype "output+no_connect"))
    )
    (net (code "69") (name "unconnected-(U11-D1-Pad29)") (class "Default")
      (node (ref "U11") (pin "29") (pinfunction "D1_29") (pintype "tri_state+no_connect"))
    )
    (net (code "70") (name "unconnected-(U11-D2-Pad32)") (class "Default")
      (node (ref "U11") (pin "32") (pinfunction "D2_32") (pintype "tri_state+no_connect"))
    )
    (net (code "71") (name "unconnected-(U11-D3-Pad33)") (class "Default")
      (node (ref "U11") (pin "33") (pinfunction "D3_33") (pintype "tri_state+no_connect"))
    )
    (net (code "72") (name "unconnected-(U11-D4-Pad43)") (class "Default")
      (node (ref "U11") (pin "43") (pinfunction "D4_43") (pintype "tri_state+no_connect"))
    )
    (net (code "73") (name "unconnected-(U11-D5-PadVCC_OUT)") (class "Default")
      (node (ref "U11") (pin "VCC_OUT") (pinfunction "D5_VCC_OUT") (pintype "tri_state+no_connect"))
    )
    (net (code "74") (name "unconnected-(U11-D6-Pad47)") (class "Default")
      (node (ref "U11") (pin "47") (pinfunction "D6_47") (pintype "tri_state+no_connect"))
    )
    (net (code "75") (name "unconnected-(U11-D7-Pad48)") (class "Default")
      (node (ref "U11") (pin "48") (pinfunction "D7_48") (pintype "tri_state+no_connect"))
    )
    (net (code "76") (name "unconnected-(U11-DNC-Pad1)") (class "Default")
      (node (ref "U11") (pin "1") (pinfunction "DNC_1") (pintype "passive+no_connect"))
    )
    (net (code "77") (name "unconnected-(U11-DNC-Pad3)") (class "Default")
      (node (ref "U11") (pin "3") (pinfunction "DNC_3") (pintype "passive+no_connect"))
    )
    (net (code "78") (name "unconnected-(U11-DNC-Pad14)") (class "Default")
      (node (ref "U11") (pin "14") (pinfunction "DNC_14") (pintype "passive+no_connect"))
    )
    (net (code "79") (name "unconnected-(U11-DNC-Pad16)") (class "Default")
      (node (ref "U11") (pin "16") (pinfunction "DNC_16") (pintype "passive+no_connect"))
    )
    (net (code "80") (name "unconnected-(U11-DNC-Pad18)") (class "Default")
      (node (ref "U11") (pin "18") (pinfunction "DNC_18") (pintype "passive+no_connect"))
    )
    (net (code "81") (name "unconnected-(U11-DNC-Pad35)") (class "Default")
      (node (ref "U11") (pin "35") (pinfunction "DNC_35") (pintype "passive+no_connect"))
    )
    (net (code "82") (name "unconnected-(U11-DNC-Pad37)") (class "Default")
      (node (ref "U11") (pin "37") (pinfunction "DNC_37") (pintype "passive+no_connect"))
    )
    (net (code "83") (name "unconnected-(U11-DNC-Pad39)") (class "Default")
      (node (ref "U11") (pin "39") (pinfunction "DNC_39") (pintype "passive+no_connect"))
    )
    (net (code "84") (name "unconnected-(U11-DNC-Pad40)") (class "Default")
      (node (ref "U11") (pin "40") (pinfunction "DNC_40") (pintype "passive+no_connect"))
    )
    (net (code "85") (name "unconnected-(U11-DNC-Pad41)") (class "Default")
      (node (ref "U11") (pin "41") (pinfunction "DNC_41") (pintype "passive+no_connect"))
    )
    (net (code "86") (name "unconnected-(U11-DNC-Pad42)") (class "Default")
      (node (ref "U11") (pin "42") (pinfunction "DNC_42") (pintype "passive+no_connect"))
    )
    (net (code "87") (name "unconnected-(U11-REV_SEL0-Pad26)") (class "Default")
      (node (ref "U11") (pin "26") (pinfunction "REV_SEL0_26") (pintype "input+no_connect"))
    )
    (net (code "88") (name "unconnected-(U11-REV_SEL1-Pad27)") (class "Default")
      (node (ref "U11") (pin "27") (pinfunction "REV_SEL1_27") (pintype "input+no_connect"))
    )
    (net (code "89") (name "unconnected-(U11-~{CEO}-Pad10)") (class "Default")
      (node (ref "U11") (pin "10") (pinfunction "~{CEO}_10") (pintype "output+no_connect"))
    )
    (net (code "90") (name "unconnected-(U11-~{CF}-Pad6)") (class "Default")
      (node (ref "U11") (pin "6") (pinfunction "~{CF}_6") (pintype "bidirectional"))
    )
    (net (code "91") (name "unconnected-(U11-~{EN_EXT_SEL}-Pad25)") (class "Default")
      (node (ref "U11") (pin "25") (pinfunction "~{EN_EXT_SEL}_25") (pintype "input+no_connect"))
    )
    (net (code "92") (name "unconnected-(U12-B5-Pad14)") (class "Default")
      (node (ref "U12") (pin "14") (pinfunction "B5_14") (pintype "bidirectional+no_connect"))
    )
    (net (code "93") (name "unconnected-(U12-B6-Pad13)") (class "Default")
      (node (ref "U12") (pin "13") (pinfunction "B6_13") (pintype "bidirectional+no_connect"))
    )
    (net (code "94") (name "unconnected-(U12-B7-Pad12)") (class "Default")
      (node (ref "U12") (pin "12") (pinfunction "B7_12") (pintype "bidirectional+no_connect"))
    )
    (net (code "95") (name "unconnected-(U12-B8-Pad11)") (class "Default")
      (node (ref "U12") (pin "11") (pinfunction "B8_11") (pintype "bidirectional+no_connect"))
    )
  )
)
